# mcu.net
KiCad netlist of a schematic drawn in Altium Designer
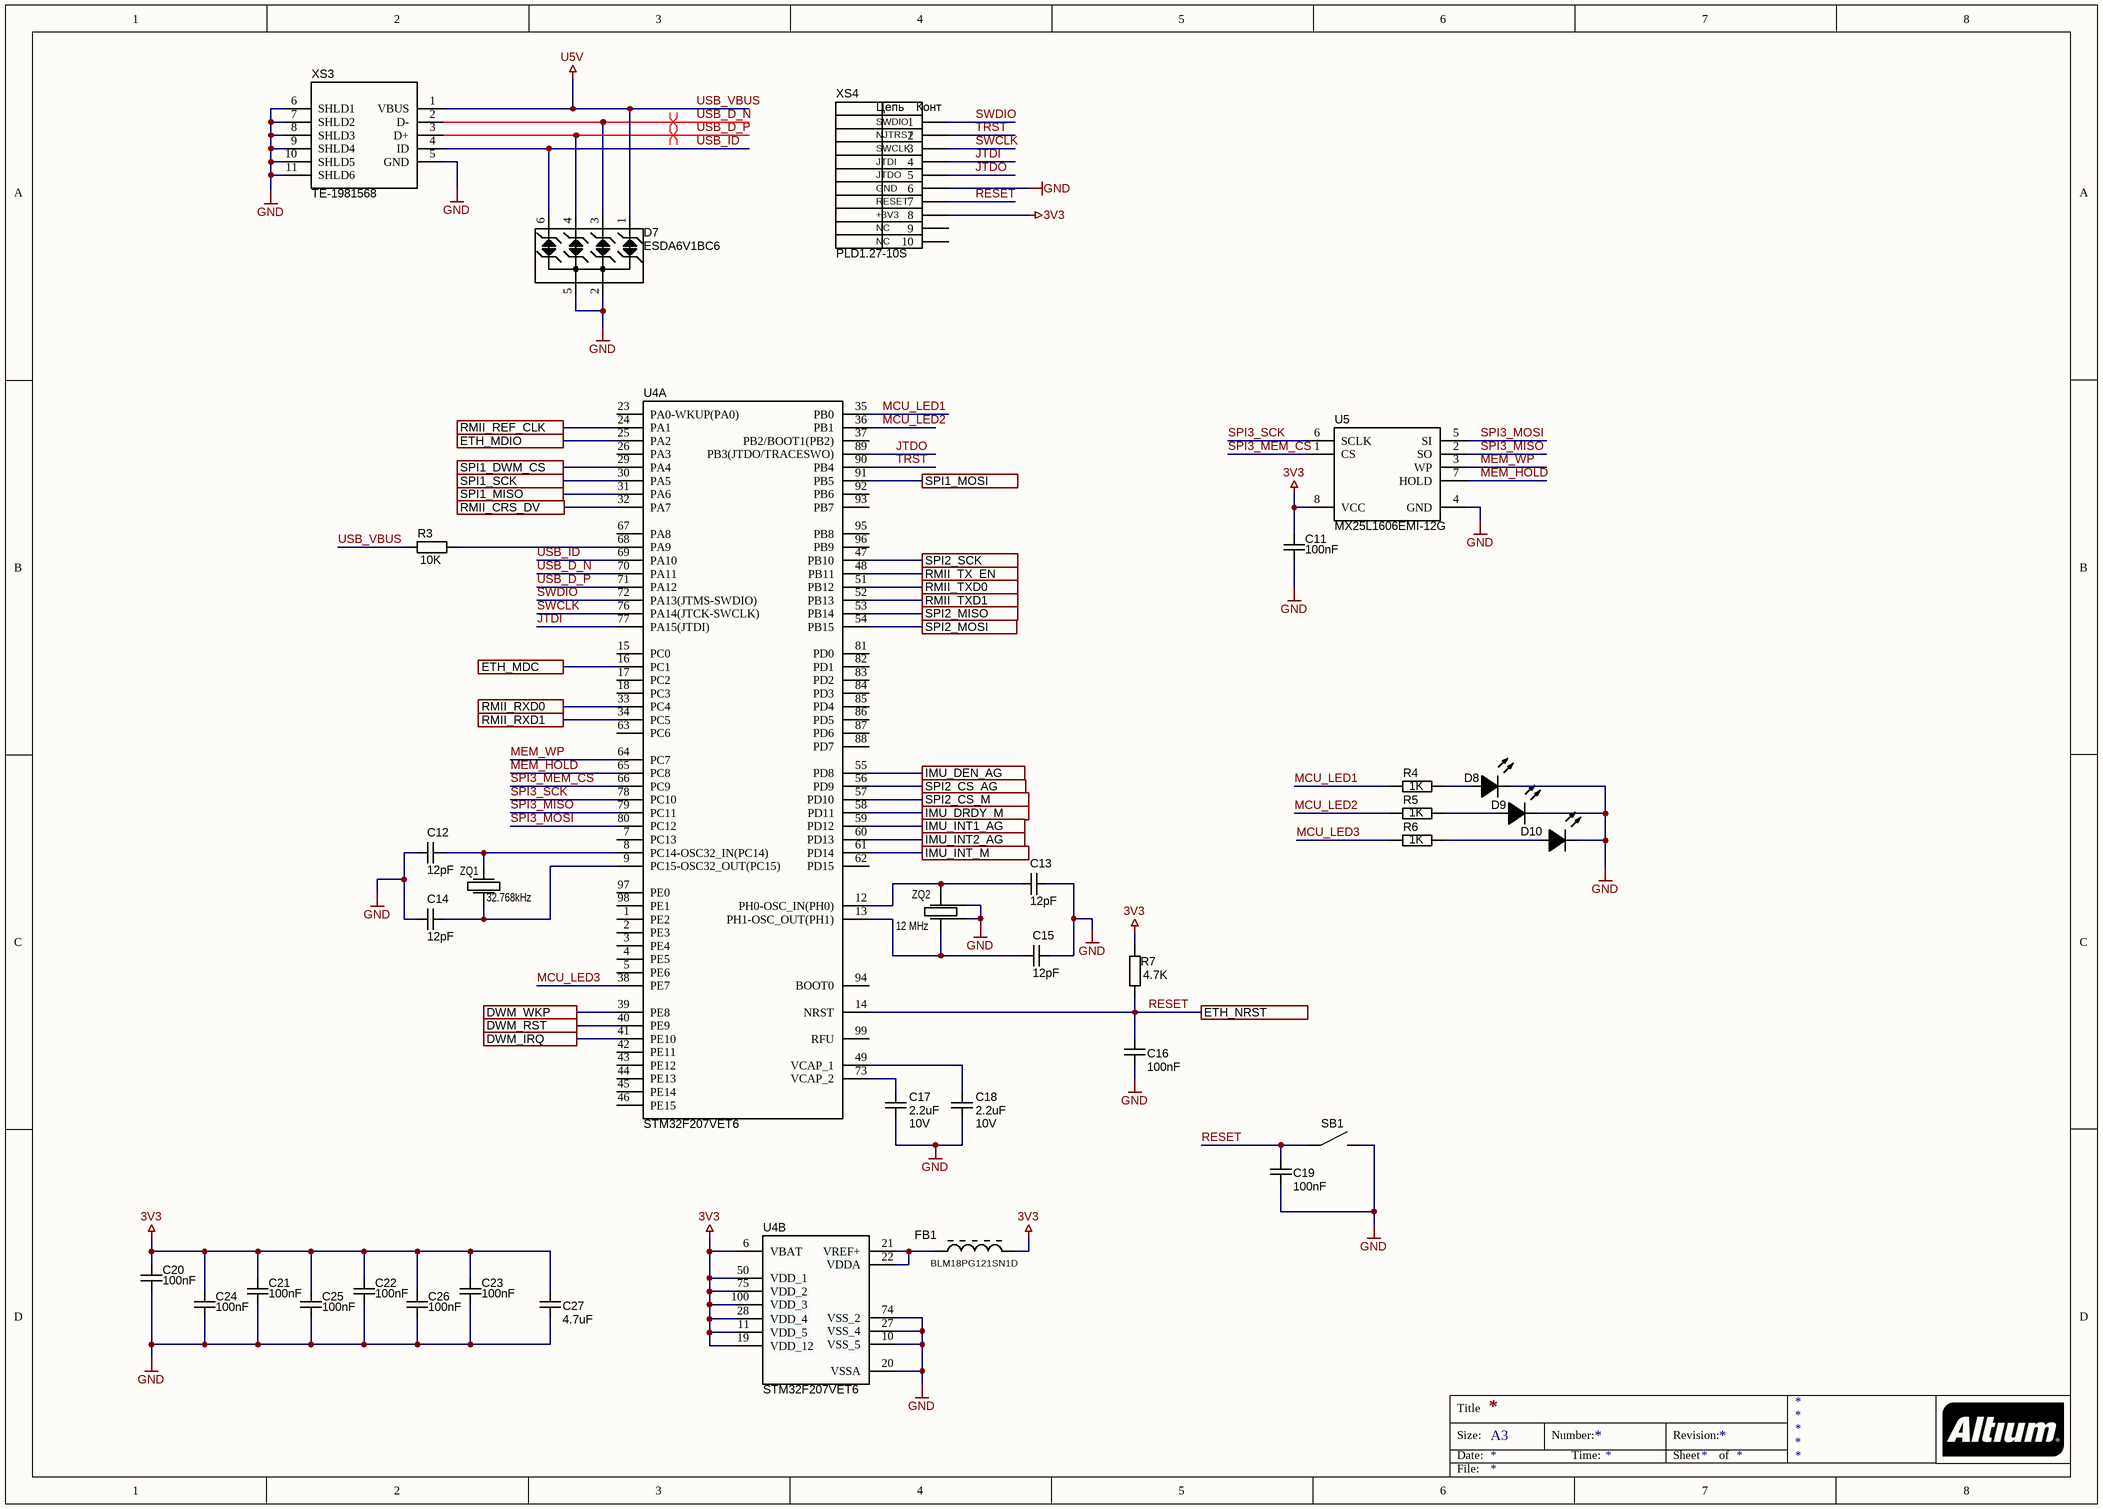
[diagram p0: mcu.SchDoc]

(export (version "E")
  (design (tool "Eeschema 10.0.6"))
  (components
    (comp (ref "C11")
      (value "100nF")
      (footprint "C0603")
      (fields (field (name "VOLTAGE") "10V") (field (name "Comment") "C0603"))
      (libsource (lib "DZ_LIB") (part "C0603"))
    )
    (comp (ref "C12")
      (value "12pF")
      (footprint "C0603")
      (fields (field (name "VOLTAGE") "*V") (field (name "Comment") "C0603"))
      (libsource (lib "DZ_LIB") (part "C0603"))
    )
    (comp (ref "C13")
      (value "12pF")
      (footprint "C0603")
      (fields (field (name "VOLTAGE") "10V") (field (name "Comment") "C0603"))
      (libsource (lib "DZ_LIB") (part "C0603"))
    )
    (comp (ref "C14")
      (value "12pF")
      (footprint "C0603")
      (fields (field (name "VOLTAGE") "*V") (field (name "Comment") "C0603"))
      (libsource (lib "DZ_LIB") (part "C0603"))
    )
    (comp (ref "C15")
      (value "12pF")
      (footprint "C0603")
      (fields (field (name "VOLTAGE") "10V") (field (name "Comment") "C0603"))
      (libsource (lib "DZ_LIB") (part "C0603"))
    )
    (comp (ref "C16")
      (value "100nF")
      (footprint "C0603")
      (fields (field (name "VOLTAGE") "10V") (field (name "Comment") "C0603"))
      (libsource (lib "DZ_LIB") (part "C0603"))
    )
    (comp (ref "C17")
      (value "2.2uF")
      (footprint "C1206(3216)")
      (fields (field (name "VOLTAGE") "10V") (field (name "Comment") "C1206"))
      (libsource (lib "DZ_LIB") (part "C1206"))
    )
    (comp (ref "C18")
      (value "2.2uF")
      (footprint "C1206(3216)")
      (fields (field (name "VOLTAGE") "10V") (field (name "Comment") "C1206"))
      (libsource (lib "DZ_LIB") (part "C1206"))
    )
    (comp (ref "C19")
      (value "100nF")
      (footprint "C0603")
      (fields (field (name "VOLTAGE") "10V") (field (name "Comment") "C0603"))
      (libsource (lib "DZ_LIB") (part "C0603"))
    )
    (comp (ref "C20")
      (value "100nF")
      (footprint "C0603")
      (fields (field (name "VOLTAGE") "10V") (field (name "Comment") "C0603"))
      (libsource (lib "DZ_LIB") (part "C0603"))
    )
    (comp (ref "C21")
      (value "100nF")
      (footprint "C0603")
      (fields (field (name "VOLTAGE") "10V") (field (name "Comment") "C0603"))
      (libsource (lib "DZ_LIB") (part "C0603"))
    )
    (comp (ref "C22")
      (value "100nF")
      (footprint "C0603")
      (fields (field (name "VOLTAGE") "10V") (field (name "Comment") "C0603"))
      (libsource (lib "DZ_LIB") (part "C0603"))
    )
    (comp (ref "C23")
      (value "100nF")
      (footprint "C0603")
      (fields (field (name "VOLTAGE") "10V") (field (name "Comment") "C0603"))
      (libsource (lib "DZ_LIB") (part "C0603"))
    )
    (comp (ref "C24")
      (value "100nF")
      (footprint "C0603")
      (fields (field (name "VOLTAGE") "10V") (field (name "Comment") "C0603"))
      (libsource (lib "DZ_LIB") (part "C0603"))
    )
    (comp (ref "C25")
      (value "100nF")
      (footprint "C0603")
      (fields (field (name "VOLTAGE") "10V") (field (name "Comment") "C0603"))
      (libsource (lib "DZ_LIB") (part "C0603"))
    )
    (comp (ref "C26")
      (value "100nF")
      (footprint "C0603")
      (fields (field (name "VOLTAGE") "10V") (field (name "Comment") "C0603"))
      (libsource (lib "DZ_LIB") (part "C0603"))
    )
    (comp (ref "C27")
      (value "4.7uF")
      (footprint "C0603")
      (fields (field (name "VOLTAGE") "10V") (field (name "Comment") "C0603"))
      (libsource (lib "DZ_LIB") (part "C0603"))
    )
    (comp (ref "D7")
      (value "ESDA6V1BC6")
      (footprint "SOT-23-6")
      (description "4-line ESD protection")
      (libsource (lib "DZ_LIB") (part "ESDA6V1BC6"))
    )
    (comp (ref "D8")
      (value "LED0805")
      (footprint "LED0805")
      (description "LED SMD 0805 K1A2")
      (libsource (lib "DZ_LIB") (part "LED0805"))
    )
    (comp (ref "D9")
      (value "LED0805")
      (footprint "LED0805")
      (description "LED SMD 0805 K1A2")
      (libsource (lib "DZ_LIB") (part "LED0805"))
    )
    (comp (ref "D10")
      (value "LED0805")
      (footprint "LED0805")
      (description "LED SMD 0805 K1A2")
      (libsource (lib "DZ_LIB") (part "LED0805"))
    )
    (comp (ref "FB1")
      (value "BLM18PG121SN1D")
      (footprint "BLM18")
      (description "Ferrite Bead 0603")
      (libsource (lib "DZ_LIB") (part "BLM18"))
    )
    (comp (ref "R3") (value "10K") (footprint "SMD0603") (libsource (lib "") (part "R0603_2")))
    (comp (ref "R4") (value "1K") (footprint "SMD0603") (libsource (lib "") (part "R0603_1")))
    (comp (ref "R5") (value "1K") (footprint "SMD0603") (libsource (lib "") (part "R0603_1")))
    (comp (ref "R6") (value "1K") (footprint "SMD0603") (libsource (lib "") (part "R0603_1")))
    (comp (ref "R7")
      (value "4.7K")
      (footprint "SMD0603")
      (fields (field (name "Comment") "R0603"))
      (libsource (lib "DZ_LIB") (part "R0603"))
    )
    (comp (ref "SB1")
      (value "FSMSM")
      (footprint "FSMSM-2")
      (description "SMD Switch 2-Leads")
      (libsource (lib "DZ_LIB") (part "FSMSM"))
    )
    (comp (ref "U4")
      (value "STM32F207VET6")
      (footprint "STM-LQFP100_V")
      (libsource (lib "") (part "STM32F207VET6_1"))
    )
    (comp (ref "U5")
      (value "MX25L1606EMI-12G")
      (footprint "SOP-8")
      (description "FLASH 16M SPI 86MHZ 16SOP")
      (libsource (lib "DZ_LIB") (part "MX25L1606EMI-12G"))
    )
    (comp (ref "XS3")
      (value "TE-1981568")
      (footprint "TECO-1981568-5_V")
      (libsource (lib "DZ_LIB") (part "USB-Micro B"))
    )
    (comp (ref "XS4")
      (value "PLD1.27-10S")
      (footprint "PLD1.27-10S")
      (libsource (lib "DZ_LIB") (part "PLD1.27-10-MCU"))
    )
    (comp (ref "ZQ1")
      (value "32.768kHz")
      (footprint "DST210A")
      (description "DST210A")
      (libsource (lib "DZ_LIB") (part "Crystal"))
    )
    (comp (ref "ZQ2")
      (value "12 MHz")
      (footprint "NX3225")
      (description "DSX321G")
      (libsource (lib "DZ_LIB") (part "Crystal_4"))
    )
  )
  (nets
    (net (code "1") (name "/DWM_IRQ") (class "Default")
      (node (ref "U4") (pin "41") (pinfunction "PE10_41") (pintype "passive"))
    )
    (net (code "2") (name "/DWM_RST") (class "Default")
      (node (ref "U4") (pin "40") (pinfunction "PE9_40") (pintype "passive"))
    )
    (net (code "3") (name "/DWM_WKP") (class "Default")
      (node (ref "U4") (pin "39") (pinfunction "PE8_39") (pintype "passive"))
    )
    (net (code "4") (name "/ETH_MDC") (class "Default")
      (node (ref "U4") (pin "16") (pinfunction "PC1_16") (pintype "passive"))
    )
    (net (code "5") (name "/ETH_MDIO") (class "Default")
      (node (ref "U4") (pin "25") (pinfunction "PA2_25") (pintype "passive"))
    )
    (net (code "6") (name "/IMU_DEN_AG") (class "Default")
      (node (ref "U4") (pin "55") (pinfunction "PD8_55") (pintype "passive"))
    )
    (net (code "7") (name "/IMU_DRDY_M") (class "Default")
      (node (ref "U4") (pin "58") (pinfunction "PD11_58") (pintype "passive"))
    )
    (net (code "8") (name "/IMU_INT1_AG") (class "Default")
      (node (ref "U4") (pin "59") (pinfunction "PD12_59") (pintype "passive"))
    )
    (net (code "9") (name "/IMU_INT2_AG") (class "Default")
      (node (ref "U4") (pin "60") (pinfunction "PD13_60") (pintype "passive"))
    )
    (net (code "10") (name "/IMU_INT_M") (class "Default")
      (node (ref "U4") (pin "61") (pinfunction "PD14_61") (pintype "passive"))
    )
    (net (code "11") (name "/JTDI") (class "Default")
      (node (ref "U4") (pin "77") (pinfunction "PA15(JTDI)_77") (pintype "passive"))
      (node (ref "XS4") (pin "4") (pinfunction "4_4") (pintype "passive"))
    )
    (net (code "12") (name "/JTDO") (class "Default")
      (node (ref "U4") (pin "89") (pinfunction "PB3(JTDO/TRACESWO)_89") (pintype "passive"))
      (node (ref "XS4") (pin "5") (pinfunction "5_5") (pintype "passive"))
    )
    (net (code "13") (name "/MCU_LED1") (class "Default")
      (node (ref "R4") (pin "2") (pinfunction "2_2") (pintype "passive"))
      (node (ref "U4") (pin "35") (pinfunction "PB0_35") (pintype "passive"))
    )
    (net (code "14") (name "/MCU_LED2") (class "Default")
      (node (ref "R5") (pin "2") (pinfunction "2_2") (pintype "passive"))
      (node (ref "U4") (pin "36") (pinfunction "PB1_36") (pintype "passive"))
    )
    (net (code "15") (name "/MCU_LED3") (class "Default")
      (node (ref "R6") (pin "2") (pinfunction "2_2") (pintype "passive"))
      (node (ref "U4") (pin "38") (pinfunction "PE7_38") (pintype "passive"))
    )
    (net (code "16") (name "/MEM_HOLD") (class "Default")
      (node (ref "U4") (pin "65") (pinfunction "PC8_65") (pintype "passive"))
      (node (ref "U5") (pin "7") (pinfunction "HOLD_7") (pintype "passive"))
    )
    (net (code "17") (name "/MEM_WP") (class "Default")
      (node (ref "U4") (pin "64") (pinfunction "PC7_64") (pintype "passive"))
      (node (ref "U5") (pin "3") (pinfunction "WP_3") (pintype "passive"))
    )
    (net (code "18") (name "/RESET") (class "Default")
      (node (ref "C16") (pin "2") (pinfunction "2_2") (pintype "passive"))
      (node (ref "C19") (pin "2") (pinfunction "2_2") (pintype "passive"))
      (node (ref "R7") (pin "1") (pinfunction "1_1") (pintype "passive"))
      (node (ref "SB1") (pin "1") (pinfunction "1_1") (pintype "passive"))
      (node (ref "U4") (pin "14") (pinfunction "NRST_14") (pintype "passive"))
      (node (ref "XS4") (pin "7") (pinfunction "7_7") (pintype "passive"))
    )
    (net (code "19") (name "/RMII_CRS_DV") (class "Default")
      (node (ref "U4") (pin "32") (pinfunction "PA7_32") (pintype "passive"))
    )
    (net (code "20") (name "/RMII_REF_CLK") (class "Default")
      (node (ref "U4") (pin "24") (pinfunction "PA1_24") (pintype "passive"))
    )
    (net (code "21") (name "/RMII_RXD0") (class "Default")
      (node (ref "U4") (pin "33") (pinfunction "PC4_33") (pintype "passive"))
    )
    (net (code "22") (name "/RMII_RXD1") (class "Default")
      (node (ref "U4") (pin "34") (pinfunction "PC5_34") (pintype "passive"))
    )
    (net (code "23") (name "/RMII_TXD0") (class "Default")
      (node (ref "U4") (pin "51") (pinfunction "PB12_51") (pintype "passive"))
    )
    (net (code "24") (name "/RMII_TXD1") (class "Default")
      (node (ref "U4") (pin "52") (pinfunction "PB13_52") (pintype "passive"))
    )
    (net (code "25") (name "/RMII_TX_EN") (class "Default")
      (node (ref "U4") (pin "48") (pinfunction "PB11_48") (pintype "passive"))
    )
    (net (code "26") (name "/SPI1_DWM_CS") (class "Default")
      (node (ref "U4") (pin "29") (pinfunction "PA4_29") (pintype "passive"))
    )
    (net (code "27") (name "/SPI1_MISO") (class "Default")
      (node (ref "U4") (pin "31") (pinfunction "PA6_31") (pintype "passive"))
    )
    (net (code "28") (name "/SPI1_MOSI") (class "Default")
      (node (ref "U4") (pin "91") (pinfunction "PB5_91") (pintype "passive"))
    )
    (net (code "29") (name "/SPI1_SCK") (class "Default")
      (node (ref "U4") (pin "30") (pinfunction "PA5_30") (pintype "passive"))
    )
    (net (code "30") (name "/SPI2_CS_AG") (class "Default")
      (node (ref "U4") (pin "56") (pinfunction "PD9_56") (pintype "passive"))
    )
    (net (code "31") (name "/SPI2_CS_M") (class "Default")
      (node (ref "U4") (pin "57") (pinfunction "PD10_57") (pintype "passive"))
    )
    (net (code "32") (name "/SPI2_MISO") (class "Default")
      (node (ref "U4") (pin "53") (pinfunction "PB14_53") (pintype "passive"))
    )
    (net (code "33") (name "/SPI2_MOSI") (class "Default")
      (node (ref "U4") (pin "54") (pinfunction "PB15_54") (pintype "passive"))
    )
    (net (code "34") (name "/SPI2_SCK") (class "Default")
      (node (ref "U4") (pin "47") (pinfunction "PB10_47") (pintype "passive"))
    )
    (net (code "35") (name "/SPI3_MEM_CS") (class "Default")
      (node (ref "U4") (pin "66") (pinfunction "PC9_66") (pintype "passive"))
      (node (ref "U5") (pin "1") (pinfunction "CS_1") (pintype "passive"))
    )
    (net (code "36") (name "/SPI3_MISO") (class "Default")
      (node (ref "U4") (pin "79") (pinfunction "PC11_79") (pintype "passive"))
      (node (ref "U5") (pin "2") (pinfunction "SO_2") (pintype "passive"))
    )
    (net (code "37") (name "/SPI3_MOSI") (class "Default")
      (node (ref "U4") (pin "80") (pinfunction "PC12_80") (pintype "passive"))
      (node (ref "U5") (pin "5") (pinfunction "SI_5") (pintype "passive"))
    )
    (net (code "38") (name "/SPI3_SCK") (class "Default")
      (node (ref "U4") (pin "78") (pinfunction "PC10_78") (pintype "passive"))
      (node (ref "U5") (pin "6") (pinfunction "SCLK_6") (pintype "passive"))
    )
    (net (code "39") (name "/SWCLK") (class "Default")
      (node (ref "U4") (pin "76") (pinfunction "PA14(JTCK-SWCLK)_76") (pintype "passive"))
      (node (ref "XS4") (pin "3") (pinfunction "3_3") (pintype "passive"))
    )
    (net (code "40") (name "/SWDIO") (class "Default")
      (node (ref "U4") (pin "72") (pinfunction "PA13(JTMS-SWDIO)_72") (pintype "passive"))
      (node (ref "XS4") (pin "1") (pinfunction "1_1") (pintype "passive"))
    )
    (net (code "41") (name "/TRST") (class "Default")
      (node (ref "U4") (pin "90") (pinfunction "PB4_90") (pintype "passive"))
      (node (ref "XS4") (pin "2") (pinfunction "2_2") (pintype "passive"))
    )
    (net (code "42") (name "/USB_D_N") (class "Default")
      (node (ref "D7") (pin "3") (pinfunction "GND_3") (pintype "passive"))
      (node (ref "U4") (pin "70") (pinfunction "PA11_70") (pintype "passive"))
      (node (ref "XS3") (pin "2") (pinfunction "D-_2") (pintype "passive"))
    )
    (net (code "43") (name "/USB_D_P") (class "Default")
      (node (ref "D7") (pin "4") (pinfunction "IO3_4") (pintype "passive"))
      (node (ref "U4") (pin "71") (pinfunction "PA12_71") (pintype "passive"))
      (node (ref "XS3") (pin "3") (pinfunction "D+_3") (pintype "passive"))
    )
    (net (code "44") (name "/USB_ID") (class "Default")
      (node (ref "D7") (pin "6") (pinfunction "NC_6") (pintype "passive"))
      (node (ref "U4") (pin "69") (pinfunction "PA10_69") (pintype "passive"))
      (node (ref "XS3") (pin "4") (pinfunction "ID_4") (pintype "passive"))
    )
    (net (code "45") (name "3V3") (class "Default")
      (node (ref "C11") (pin "2") (pinfunction "2_2") (pintype "passive"))
      (node (ref "C20") (pin "2") (pinfunction "2_2") (pintype "passive"))
      (node (ref "C21") (pin "2") (pinfunction "2_2") (pintype "passive"))
      (node (ref "C22") (pin "2") (pinfunction "2_2") (pintype "passive"))
      (node (ref "C23") (pin "2") (pinfunction "2_2") (pintype "passive"))
      (node (ref "C24") (pin "2") (pinfunction "2_2") (pintype "passive"))
      (node (ref "C25") (pin "2") (pinfunction "2_2") (pintype "passive"))
      (node (ref "C26") (pin "2") (pinfunction "2_2") (pintype "passive"))
      (node (ref "C27") (pin "1") (pinfunction "1_1") (pintype "passive"))
      (node (ref "FB1") (pin "2") (pinfunction "2_2") (pintype "passive"))
      (node (ref "R7") (pin "2") (pinfunction "2_2") (pintype "passive"))
      (node (ref "U4") (pin "100") (pinfunction "VDD_3_100") (pintype "power_in"))
      (node (ref "U4") (pin "11") (pinfunction "VDD_5_11") (pintype "power_in"))
      (node (ref "U4") (pin "19") (pinfunction "VDD_12_19") (pintype "power_in"))
      (node (ref "U4") (pin "28") (pinfunction "VDD_4_28") (pintype "power_in"))
      (node (ref "U4") (pin "50") (pinfunction "VDD_1_50") (pintype "power_in"))
      (node (ref "U4") (pin "6") (pinfunction "VBAT_6") (pintype "power_in"))
      (node (ref "U4") (pin "75") (pinfunction "VDD_2_75") (pintype "power_in"))
      (node (ref "U5") (pin "8") (pinfunction "VCC_8") (pintype "passive"))
      (node (ref "XS4") (pin "8") (pinfunction "8_8") (pintype "passive"))
    )
    (net (code "46") (name "GND") (class "Default")
      (node (ref "C11") (pin "1") (pinfunction "1_1") (pintype "passive"))
      (node (ref "C12") (pin "1") (pinfunction "1_1") (pintype "passive"))
      (node (ref "C13") (pin "2") (pinfunction "2_2") (pintype "passive"))
      (node (ref "C14") (pin "1") (pinfunction "1_1") (pintype "passive"))
      (node (ref "C15") (pin "2") (pinfunction "2_2") (pintype "passive"))
      (node (ref "C16") (pin "1") (pinfunction "1_1") (pintype "passive"))
      (node (ref "C17") (pin "1") (pinfunction "1_1") (pintype "passive"))
      (node (ref "C18") (pin "1") (pinfunction "1_1") (pintype "passive"))
      (node (ref "C19") (pin "1") (pinfunction "1_1") (pintype "passive"))
      (node (ref "C20") (pin "1") (pinfunction "1_1") (pintype "passive"))
      (node (ref "C21") (pin "1") (pinfunction "1_1") (pintype "passive"))
      (node (ref "C22") (pin "1") (pinfunction "1_1") (pintype "passive"))
      (node (ref "C23") (pin "1") (pinfunction "1_1") (pintype "passive"))
      (node (ref "C24") (pin "1") (pinfunction "1_1") (pintype "passive"))
      (node (ref "C25") (pin "1") (pinfunction "1_1") (pintype "passive"))
      (node (ref "C26") (pin "1") (pinfunction "1_1") (pintype "passive"))
      (node (ref "C27") (pin "2") (pinfunction "2_2") (pintype "passive"))
      (node (ref "D10") (pin "1") (pinfunction "K_1") (pintype "passive"))
      (node (ref "D7") (pin "2") (pinfunction "IO2_2") (pintype "passive"))
      (node (ref "D7") (pin "5") (pinfunction "IO4_5") (pintype "passive"))
      (node (ref "D8") (pin "1") (pinfunction "K_1") (pintype "passive"))
      (node (ref "D9") (pin "1") (pinfunction "K_1") (pintype "passive"))
      (node (ref "SB1") (pin "2") (pinfunction "2_2") (pintype "passive"))
      (node (ref "U4") (pin "10") (pinfunction "VSS_5_10") (pintype "power_in"))
      (node (ref "U4") (pin "20") (pinfunction "VSSA_20") (pintype "power_in"))
      (node (ref "U4") (pin "27") (pinfunction "VSS_4_27") (pintype "power_in"))
      (node (ref "U4") (pin "74") (pinfunction "VSS_2_74") (pintype "power_in"))
      (node (ref "U5") (pin "4") (pinfunction "GND_4") (pintype "passive"))
      (node (ref "XS3") (pin "10") (pinfunction "SHLD5_10") (pintype "passive"))
      (node (ref "XS3") (pin "11") (pinfunction "SHLD6_11") (pintype "passive"))
      (node (ref "XS3") (pin "5") (pinfunction "GND_5") (pintype "passive"))
      (node (ref "XS3") (pin "6") (pinfunction "SHLD1_6") (pintype "passive"))
      (node (ref "XS3") (pin "7") (pinfunction "SHLD2_7") (pintype "passive"))
      (node (ref "XS3") (pin "8") (pinfunction "SHLD3_8") (pintype "passive"))
      (node (ref "XS3") (pin "9") (pinfunction "SHLD4_9") (pintype "passive"))
      (node (ref "XS4") (pin "6") (pinfunction "6_6") (pintype "passive"))
      (node (ref "ZQ2") (pin "2") (pinfunction "2_2") (pintype "passive"))
      (node (ref "ZQ2") (pin "4") (pinfunction "4_4") (pintype "passive"))
    )
    (net (code "47") (name "Net-(D8-A)") (class "Default")
      (node (ref "D8") (pin "2") (pinfunction "A_2") (pintype "passive"))
      (node (ref "R4") (pin "1") (pinfunction "1_1") (pintype "passive"))
    )
    (net (code "48") (name "Net-(D9-A)") (class "Default")
      (node (ref "D9") (pin "2") (pinfunction "A_2") (pintype "passive"))
      (node (ref "R5") (pin "1") (pinfunction "1_1") (pintype "passive"))
    )
    (net (code "49") (name "Net-(D10-A)") (class "Default")
      (node (ref "D10") (pin "2") (pinfunction "A_2") (pintype "passive"))
      (node (ref "R6") (pin "1") (pinfunction "1_1") (pintype "passive"))
    )
    (net (code "50") (name "Net-(U4A-PA9)") (class "Default")
      (node (ref "R3") (pin "2") (pinfunction "2_2") (pintype "passive"))
      (node (ref "U4") (pin "68") (pinfunction "PA9_68") (pintype "passive"))
    )
    (net (code "51") (name "Net-(U4A-PC14-OSC32_IN(PC14))") (class "Default")
      (node (ref "C12") (pin "2") (pinfunction "2_2") (pintype "passive"))
      (node (ref "U4") (pin "8") (pinfunction "PC14-OSC32_IN(PC14)_8") (pintype "passive"))
      (node (ref "ZQ1") (pin "2") (pinfunction "OSC2_2") (pintype "passive"))
    )
    (net (code "52") (name "Net-(U4A-PC15-OSC32_OUT(PC15))") (class "Default")
      (node (ref "C14") (pin "2") (pinfunction "2_2") (pintype "passive"))
      (node (ref "U4") (pin "9") (pinfunction "PC15-OSC32_OUT(PC15)_9") (pintype "passive"))
      (node (ref "ZQ1") (pin "1") (pinfunction "OSC1_1") (pintype "passive"))
    )
    (net (code "53") (name "Net-(U4A-PH0-OSC_IN(PH0))") (class "Default")
      (node (ref "C13") (pin "1") (pinfunction "1_1") (pintype "passive"))
      (node (ref "U4") (pin "12") (pinfunction "PH0-OSC_IN(PH0)_12") (pintype "passive"))
      (node (ref "ZQ2") (pin "3") (pinfunction "3_3") (pintype "passive"))
    )
    (net (code "54") (name "Net-(U4A-PH1-OSC_OUT(PH1))") (class "Default")
      (node (ref "C15") (pin "1") (pinfunction "1_1") (pintype "passive"))
      (node (ref "U4") (pin "13") (pinfunction "PH1-OSC_OUT(PH1)_13") (pintype "passive"))
      (node (ref "ZQ2") (pin "1") (pinfunction "1_1") (pintype "passive"))
    )
    (net (code "55") (name "Net-(U4A-VCAP_1)") (class "Default")
      (node (ref "C18") (pin "2") (pinfunction "2_2") (pintype "passive"))
      (node (ref "U4") (pin "49") (pinfunction "VCAP_1_49") (pintype "passive"))
    )
    (net (code "56") (name "Net-(U4A-VCAP_2)") (class "Default")
      (node (ref "C17") (pin "2") (pinfunction "2_2") (pintype "passive"))
      (node (ref "U4") (pin "73") (pinfunction "VCAP_2_73") (pintype "passive"))
    )
    (net (code "57") (name "Net-(U4B-VDDA)") (class "Default")
      (node (ref "FB1") (pin "1") (pinfunction "1_1") (pintype "passive"))
      (node (ref "U4") (pin "21") (pinfunction "VREF+_21") (pintype "power_in"))
      (node (ref "U4") (pin "22") (pinfunction "VDDA_22") (pintype "power_in"))
    )
    (net (code "58") (name "U5V") (class "Default")
      (node (ref "D7") (pin "1") (pinfunction "IO1_1") (pintype "passive"))
      (node (ref "R3") (pin "1") (pinfunction "1_1") (pintype "passive"))
      (node (ref "XS3") (pin "1") (pinfunction "VBUS_1") (pintype "passive"))
    )
    (net (code "59") (name "unconnected-(U4A-BOOT0-Pad94)") (class "Default")
      (node (ref "U4") (pin "94") (pinfunction "BOOT0_94") (pintype "passive"))
    )
    (net (code "60") (name "unconnected-(U4A-PA0-WKUP(PA0)-Pad23)") (class "Default")
      (node (ref "U4") (pin "23") (pinfunction "PA0-WKUP(PA0)_23") (pintype "passive"))
    )
    (net (code "61") (name "unconnected-(U4A-PA3-Pad26)") (class "Default")
      (node (ref "U4") (pin "26") (pinfunction "PA3_26") (pintype "passive"))
    )
    (net (code "62") (name "unconnected-(U4A-PA8-Pad67)") (class "Default")
      (node (ref "U4") (pin "67") (pinfunction "PA8_67") (pintype "passive"))
    )
    (net (code "63") (name "unconnected-(U4A-PB2{slash}BOOT1(PB2)-Pad37)") (class "Default")
      (node (ref "U4") (pin "37") (pinfunction "PB2/BOOT1(PB2)_37") (pintype "passive"))
    )
    (net (code "64") (name "unconnected-(U4A-PB6-Pad92)") (class "Default")
      (node (ref "U4") (pin "92") (pinfunction "PB6_92") (pintype "passive"))
    )
    (net (code "65") (name "unconnected-(U4A-PB7-Pad93)") (class "Default")
      (node (ref "U4") (pin "93") (pinfunction "PB7_93") (pintype "passive"))
    )
    (net (code "66") (name "unconnected-(U4A-PB8-Pad95)") (class "Default")
      (node (ref "U4") (pin "95") (pinfunction "PB8_95") (pintype "passive"))
    )
    (net (code "67") (name "unconnected-(U4A-PB9-Pad96)") (class "Default")
      (node (ref "U4") (pin "96") (pinfunction "PB9_96") (pintype "passive"))
    )
    (net (code "68") (name "unconnected-(U4A-PC0-Pad15)") (class "Default")
      (node (ref "U4") (pin "15") (pinfunction "PC0_15") (pintype "passive"))
    )
    (net (code "69") (name "unconnected-(U4A-PC2-Pad17)") (class "Default")
      (node (ref "U4") (pin "17") (pinfunction "PC2_17") (pintype "passive"))
    )
    (net (code "70") (name "unconnected-(U4A-PC3-Pad18)") (class "Default")
      (node (ref "U4") (pin "18") (pinfunction "PC3_18") (pintype "passive"))
    )
    (net (code "71") (name "unconnected-(U4A-PC6-Pad63)") (class "Default")
      (node (ref "U4") (pin "63") (pinfunction "PC6_63") (pintype "passive"))
    )
    (net (code "72") (name "unconnected-(U4A-PC13-Pad7)") (class "Default")
      (node (ref "U4") (pin "7") (pinfunction "PC13_7") (pintype "passive"))
    )
    (net (code "73") (name "unconnected-(U4A-PD0-Pad81)") (class "Default")
      (node (ref "U4") (pin "81") (pinfunction "PD0_81") (pintype "passive"))
    )
    (net (code "74") (name "unconnected-(U4A-PD1-Pad82)") (class "Default")
      (node (ref "U4") (pin "82") (pinfunction "PD1_82") (pintype "passive"))
    )
    (net (code "75") (name "unconnected-(U4A-PD2-Pad83)") (class "Default")
      (node (ref "U4") (pin "83") (pinfunction "PD2_83") (pintype "passive"))
    )
    (net (code "76") (name "unconnected-(U4A-PD3-Pad84)") (class "Default")
      (node (ref "U4") (pin "84") (pinfunction "PD3_84") (pintype "passive"))
    )
    (net (code "77") (name "unconnected-(U4A-PD4-Pad85)") (class "Default")
      (node (ref "U4") (pin "85") (pinfunction "PD4_85") (pintype "passive"))
    )
    (net (code "78") (name "unconnected-(U4A-PD5-Pad86)") (class "Default")
      (node (ref "U4") (pin "86") (pinfunction "PD5_86") (pintype "passive"))
    )
    (net (code "79") (name "unconnected-(U4A-PD6-Pad87)") (class "Default")
      (node (ref "U4") (pin "87") (pinfunction "PD6_87") (pintype "passive"))
    )
    (net (code "80") (name "unconnected-(U4A-PD7-Pad88)") (class "Default")
      (node (ref "U4") (pin "88") (pinfunction "PD7_88") (pintype "passive"))
    )
    (net (code "81") (name "unconnected-(U4A-PD15-Pad62)") (class "Default")
      (node (ref "U4") (pin "62") (pinfunction "PD15_62") (pintype "passive"))
    )
    (net (code "82") (name "unconnected-(U4A-PE0-Pad97)") (class "Default")
      (node (ref "U4") (pin "97") (pinfunction "PE0_97") (pintype "passive"))
    )
    (net (code "83") (name "unconnected-(U4A-PE1-Pad98)") (class "Default")
      (node (ref "U4") (pin "98") (pinfunction "PE1_98") (pintype "passive"))
    )
    (net (code "84") (name "unconnected-(U4A-PE2-Pad1)") (class "Default")
      (node (ref "U4") (pin "1") (pinfunction "PE2_1") (pintype "passive"))
    )
    (net (code "85") (name "unconnected-(U4A-PE3-Pad2)") (class "Default")
      (node (ref "U4") (pin "2") (pinfunction "PE3_2") (pintype "passive"))
    )
    (net (code "86") (name "unconnected-(U4A-PE4-Pad3)") (class "Default")
      (node (ref "U4") (pin "3") (pinfunction "PE4_3") (pintype "passive"))
    )
    (net (code "87") (name "unconnected-(U4A-PE5-Pad4)") (class "Default")
      (node (ref "U4") (pin "4") (pinfunction "PE5_4") (pintype "passive"))
    )
    (net (code "88") (name "unconnected-(U4A-PE6-Pad5)") (class "Default")
      (node (ref "U4") (pin "5") (pinfunction "PE6_5") (pintype "passive"))
    )
    (net (code "89") (name "unconnected-(U4A-PE11-Pad42)") (class "Default")
      (node (ref "U4") (pin "42") (pinfunction "PE11_42") (pintype "passive"))
    )
    (net (code "90") (name "unconnected-(U4A-PE12-Pad43)") (class "Default")
      (node (ref "U4") (pin "43") (pinfunction "PE12_43") (pintype "passive"))
    )
    (net (code "91") (name "unconnected-(U4A-PE13-Pad44)") (class "Default")
      (node (ref "U4") (pin "44") (pinfunction "PE13_44") (pintype "passive"))
    )
    (net (code "92") (name "unconnected-(U4A-PE14-Pad45)") (class "Default")
      (node (ref "U4") (pin "45") (pinfunction "PE14_45") (pintype "passive"))
    )
    (net (code "93") (name "unconnected-(U4A-PE15-Pad46)") (class "Default")
      (node (ref "U4") (pin "46") (pinfunction "PE15_46") (pintype "passive"))
    )
    (net (code "94") (name "unconnected-(U4A-RFU-Pad99)") (class "Default")
      (node (ref "U4") (pin "99") (pinfunction "RFU_99") (pintype "passive"))
    )
    (net (code "95") (name "unconnected-(XS4-Pad9)") (class "Default")
      (node (ref "XS4") (pin "9") (pinfunction "9_9") (pintype "passive"))
    )
    (net (code "96") (name "unconnected-(XS4-Pad10)") (class "Default")
      (node (ref "XS4") (pin "10") (pinfunction "10_10") (pintype "passive"))
    )
  )
)
